# RAIL_DISCHARGE.net
KiCad netlist of a schematic drawn in Altium Designer
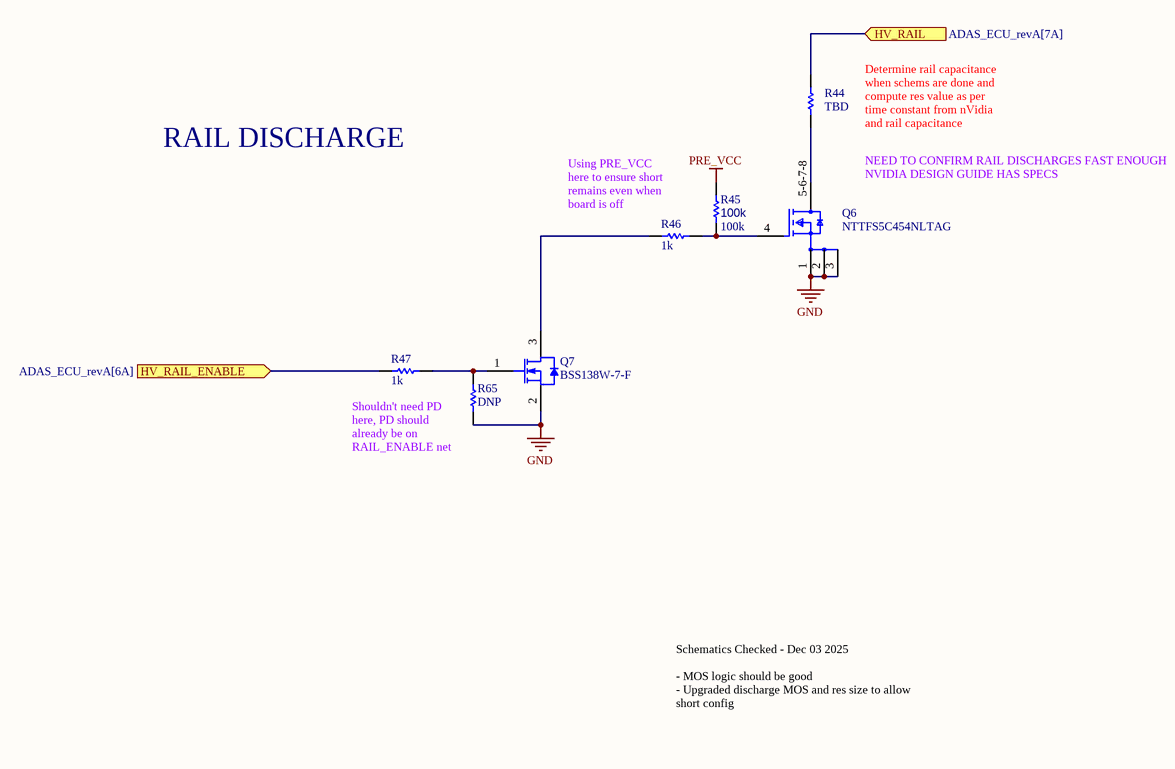
[diagram p0: RAIL_DISCHARGE.SchDoc]

(export (version "E")
  (design (tool "Eeschema 10.0.6"))
  (components
    (comp (ref "Q6")
      (value "NTTFS5C454NLTAG")
      (footprint "FP-511AB-MFG")
      (libsource (lib "Altium Content Vault") (part "7382af88e928fdc71488234cfaaf11c"))
    )
    (comp (ref "Q7")
      (value "BSS138W-7-F")
      (footprint "DIOD-SOT323-3_V")
      (fields (field (name "MANUFACTURER") "DiodesIncorporated"))
      (libsource (lib "Altium Content Vault") (part "NEMOS-GSD-3"))
    )
    (comp (ref "R44")
      (value "TBD")
      (footprint "R1206B")
      (description "Resistor")
      (libsource (lib "Space Concordia") (part "Resistor"))
    )
    (comp (ref "R45")
      (value "100k")
      (footprint "R0603B")
      (description "Resistor")
      (fields (field (name "ALTIUM_VALUE") "100k"))
      (libsource (lib "Space Concordia") (part "Resistor"))
    )
    (comp (ref "R46")
      (value "1k")
      (footprint "R0603B")
      (description "Resistor")
      (libsource (lib "Space Concordia") (part "Resistor"))
    )
    (comp (ref "R47")
      (value "1k")
      (footprint "R0603B")
      (description "Resistor")
      (libsource (lib "Space Concordia") (part "Resistor"))
    )
    (comp (ref "R65")
      (value "DNP")
      (footprint "R0603B")
      (description "Resistor")
      (libsource (lib "Space Concordia") (part "Resistor"))
    )
  )
  (nets
    (net (code "1") (name "/HV_RAIL") (class "Default")
      (node (ref "R44") (pin "1") (pinfunction "1_1") (pintype "passive"))
    )
    (net (code "2") (name "/HV_RAIL_ENABLE") (class "Default")
      (node (ref "R47") (pin "2") (pinfunction "2_2") (pintype "passive"))
    )
    (net (code "3") (name "GND") (class "Default")
      (node (ref "Q6") (pin "1") (pinfunction "S_1") (pintype "passive"))
      (node (ref "Q6") (pin "2") (pinfunction "S_2") (pintype "passive"))
      (node (ref "Q6") (pin "3") (pinfunction "S_3") (pintype "passive"))
      (node (ref "Q7") (pin "2") (pinfunction "S_2") (pintype "passive"))
      (node (ref "R65") (pin "2") (pinfunction "2_2") (pintype "passive"))
    )
    (net (code "4") (name "Net-(Q6-D)") (class "Default")
      (node (ref "Q6") (pin "5-6-7-8") (pinfunction "D_5-6-7-8") (pintype "passive"))
      (node (ref "R44") (pin "2") (pinfunction "2_2") (pintype "passive"))
    )
    (net (code "5") (name "Net-(Q6-G)") (class "Default")
      (node (ref "Q6") (pin "4") (pinfunction "G_4") (pintype "passive"))
      (node (ref "R45") (pin "1") (pinfunction "1_1") (pintype "passive"))
      (node (ref "R46") (pin "2") (pinfunction "2_2") (pintype "passive"))
    )
    (net (code "6") (name "Net-(Q7-D)") (class "Default")
      (node (ref "Q7") (pin "3") (pinfunction "D_3") (pintype "passive"))
      (node (ref "R46") (pin "1") (pinfunction "1_1") (pintype "passive"))
    )
    (net (code "7") (name "Net-(Q7-G)") (class "Default")
      (node (ref "Q7") (pin "1") (pinfunction "G_1") (pintype "passive"))
      (node (ref "R47") (pin "1") (pinfunction "1_1") (pintype "passive"))
      (node (ref "R65") (pin "1") (pinfunction "1_1") (pintype "passive"))
    )
    (net (code "8") (name "PRE_VCC") (class "Default")
      (node (ref "R45") (pin "2") (pinfunction "2_2") (pintype "passive"))
    )
  )
)
